# FioSaber.net
KiCad netlist of a schematic drawn in EAGLE
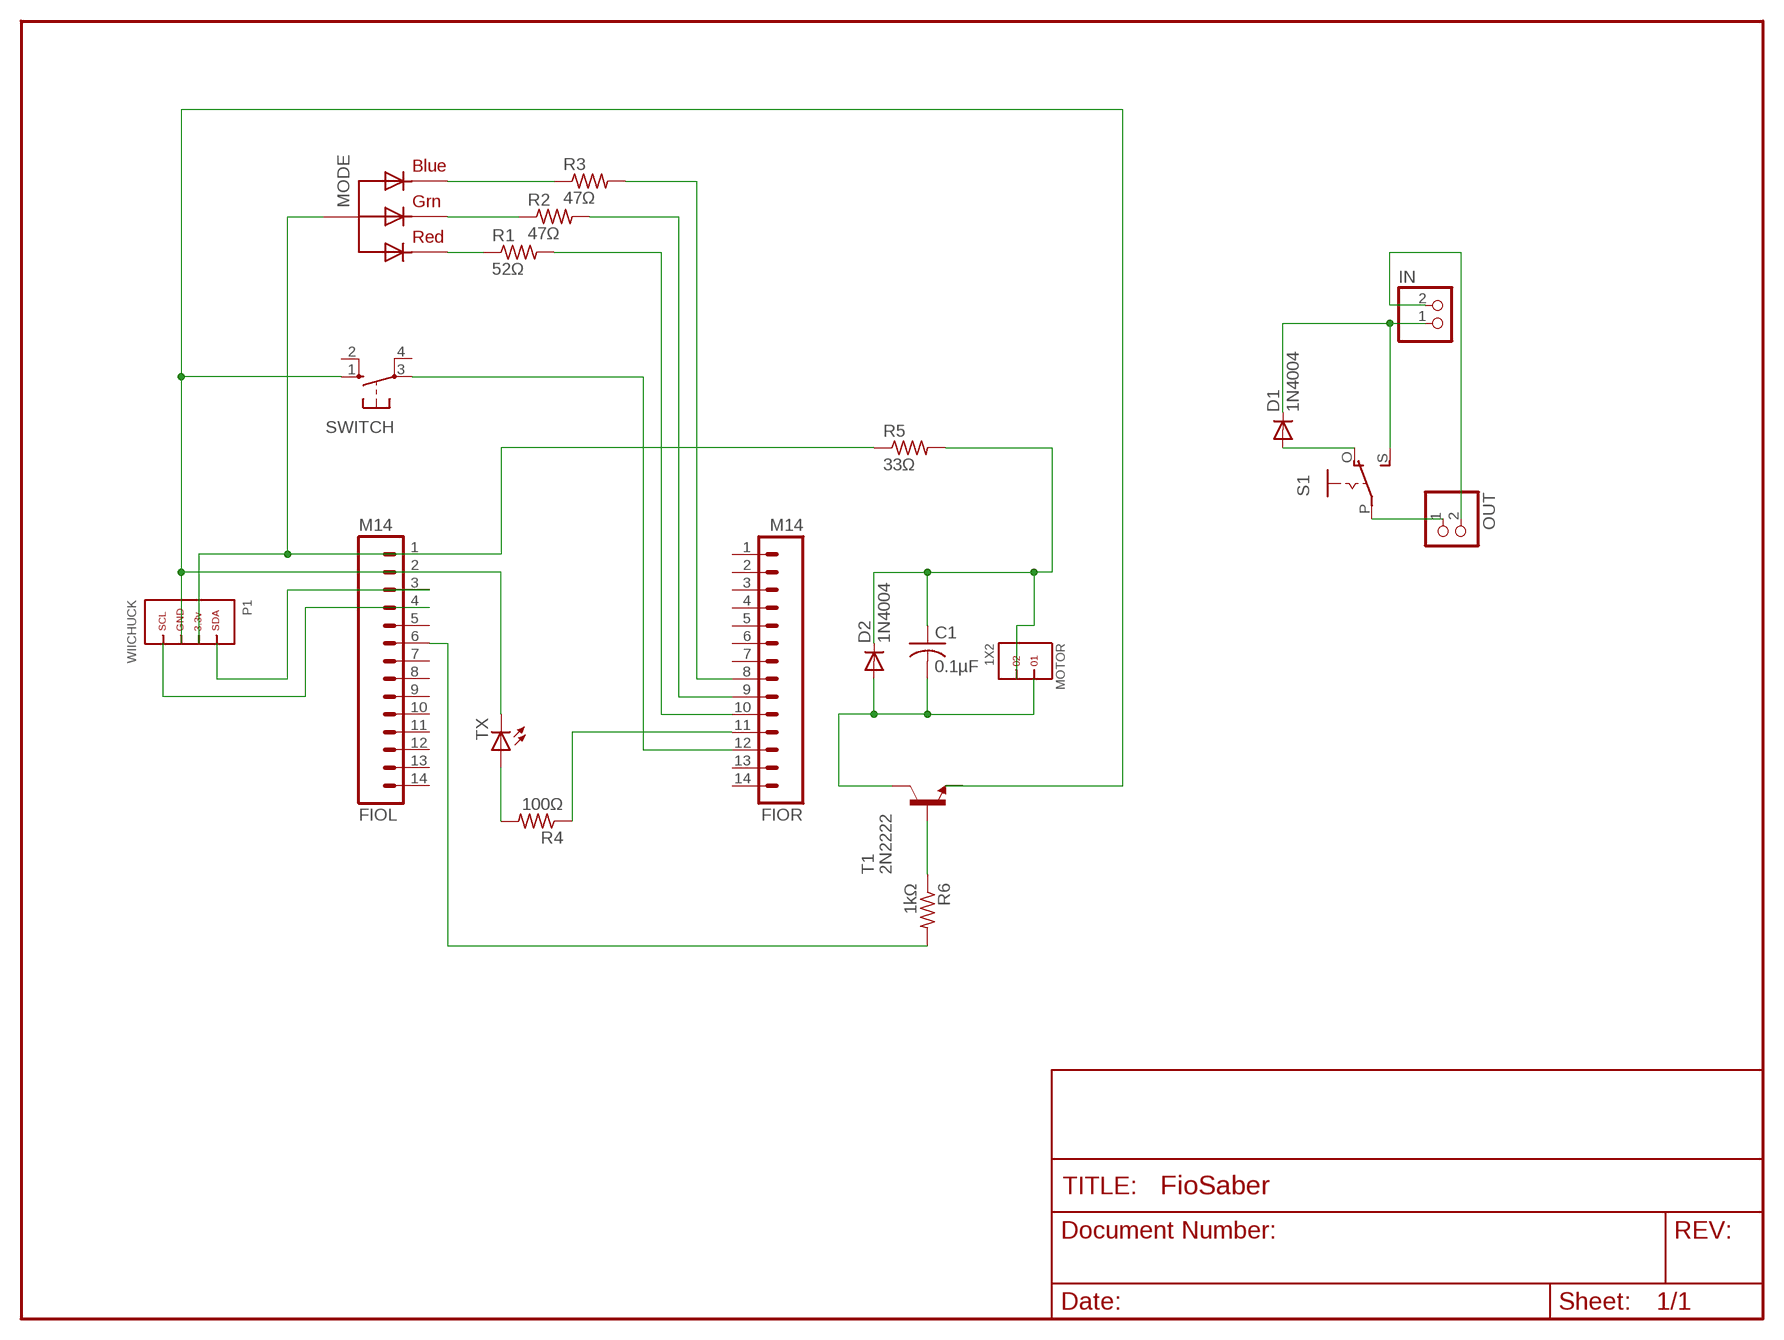
[diagram p0: schematic, sheet 1]

(export (version "E")
  (design (tool "Eeschema 10.0.6"))
  (components
    (comp (ref "C1")
      (value "0.1µF")
      (footprint "eagle-import:C025-025X050")
      (libsource (lib "eagle-import") (part "C-US025-025X050"))
    )
    (comp (ref "D1")
      (value "1N4004")
      (footprint "eagle-import:DO41-10")
      (libsource (lib "eagle-import") (part "1N4004"))
    )
    (comp (ref "D2")
      (value "1N4004")
      (footprint "eagle-import:DO41-10")
      (libsource (lib "eagle-import") (part "1N4004"))
    )
    (comp (ref "FIOL")
      (value "M14")
      (footprint "eagle-import:1X14")
      (libsource (lib "eagle-import") (part "M14"))
    )
    (comp (ref "FIOR")
      (value "M14")
      (footprint "eagle-import:1X14")
      (libsource (lib "eagle-import") (part "M14"))
    )
    (comp (ref "IN")
      (value "JST_2PIN-THM-RA")
      (footprint "eagle-import:JST-PH-2-THM-RA")
      (libsource (lib "eagle-import") (part "JST_2PIN-THM-RA"))
    )
    (comp (ref "MODE")
      (value "RGBLED_CA-PIRANHA")
      (footprint "eagle-import:PIRANHA5MM")
      (libsource (lib "eagle-import") (part "RGBLED_CA-PIRANHA"))
    )
    (comp (ref "MOTOR")
      (value "1X2")
      (footprint "eagle-import:1X2")
      (libsource (lib "eagle-import") (part "1X2"))
    )
    (comp (ref "OUT")
      (value "JST_2PIN-THM-RA")
      (footprint "eagle-import:JST-PH-2-THM-RA")
      (libsource (lib "eagle-import") (part "JST_2PIN-THM-RA"))
    )
    (comp (ref "P1")
      (value "WIICHUCK")
      (footprint "eagle-import:MEMOREX_RECEIVER")
      (libsource (lib "eagle-import") (part "WIICHUCK"))
    )
    (comp (ref "R1")
      (value "52Ω")
      (footprint "eagle-import:0207_7")
      (libsource (lib "eagle-import") (part "R-US_0207/7"))
    )
    (comp (ref "R2")
      (value "47Ω")
      (footprint "eagle-import:0207_7")
      (libsource (lib "eagle-import") (part "R-US_0207/7"))
    )
    (comp (ref "R3")
      (value "47Ω")
      (footprint "eagle-import:0207_7")
      (libsource (lib "eagle-import") (part "R-US_0207/7"))
    )
    (comp (ref "R4")
      (value "100Ω")
      (footprint "eagle-import:0207_7")
      (libsource (lib "eagle-import") (part "R-US_0207/7"))
    )
    (comp (ref "R5")
      (value "33Ω")
      (footprint "eagle-import:0207_7")
      (libsource (lib "eagle-import") (part "R-US_0207/7"))
    )
    (comp (ref "R6")
      (value "1kΩ")
      (footprint "eagle-import:0207_7")
      (libsource (lib "eagle-import") (part "R-US_0207/7"))
    )
    (comp (ref "S1")
      (value "EG1218S")
      (footprint "eagle-import:EG1218")
      (libsource (lib "eagle-import") (part "EG1218S"))
    )
    (comp (ref "SWITCH")
      (value "10-XX")
      (footprint "eagle-import:B3F-10XX")
      (fields (field (name "MPN") "B3F-1000"))
      (libsource (lib "eagle-import") (part "10-XX"))
    )
    (comp (ref "T1")
      (value "2N2222")
      (footprint "eagle-import:TO92-EBC-OVAL")
      (libsource (lib "eagle-import") (part "2N2222"))
    )
    (comp (ref "TX")
      (value "LED3MM")
      (footprint "eagle-import:LED3MM")
      (libsource (lib "eagle-import") (part "LED3MM"))
    )
  )
  (nets
    (net (code "1") (name "Net-(C1-Pad1)") (class "Default")
      (node (ref "C1") (pin "1") (pinfunction "1_1") (pintype "passive"))
      (node (ref "D2") (pin "C") (pinfunction "C_C") (pintype "passive"))
      (node (ref "MOTOR") (pin "2") (pinfunction "2_2") (pintype "bidirectional"))
      (node (ref "R5") (pin "2") (pinfunction "2_2") (pintype "passive"))
    )
    (net (code "2") (name "Net-(C1-Pad2)") (class "Default")
      (node (ref "C1") (pin "2") (pinfunction "2_2") (pintype "passive"))
      (node (ref "D2") (pin "A") (pinfunction "A_A") (pintype "passive"))
      (node (ref "MOTOR") (pin "1") (pinfunction "1_1") (pintype "bidirectional"))
      (node (ref "T1") (pin "C") (pinfunction "C_C") (pintype "passive"))
    )
    (net (code "3") (name "Net-(D1-PadA)") (class "Default")
      (node (ref "D1") (pin "A") (pinfunction "A_A") (pintype "passive"))
      (node (ref "S1") (pin "O") (pinfunction "O_O") (pintype "passive"))
    )
    (net (code "4") (name "Net-(FIOL-Pad3)") (class "Default")
      (node (ref "FIOL") (pin "3") (pinfunction "3_3") (pintype "passive"))
      (node (ref "P1") (pin "PWR") (pinfunction "PWR_PWR") (pintype "bidirectional"))
    )
    (net (code "5") (name "Net-(FIOL-Pad4)") (class "Default")
      (node (ref "FIOL") (pin "4") (pinfunction "4_4") (pintype "passive"))
      (node (ref "P1") (pin "GND") (pinfunction "GND_GND") (pintype "bidirectional"))
    )
    (net (code "6") (name "Net-(FIOL-Pad6)") (class "Default")
      (node (ref "FIOL") (pin "6") (pinfunction "6_6") (pintype "passive"))
      (node (ref "R6") (pin "2") (pinfunction "2_2") (pintype "passive"))
    )
    (net (code "7") (name "Net-(FIOR-Pad8)") (class "Default")
      (node (ref "FIOR") (pin "8") (pinfunction "8_8") (pintype "passive"))
      (node (ref "R3") (pin "2") (pinfunction "2_2") (pintype "passive"))
    )
    (net (code "8") (name "Net-(FIOR-Pad9)") (class "Default")
      (node (ref "FIOR") (pin "9") (pinfunction "9_9") (pintype "passive"))
      (node (ref "R2") (pin "2") (pinfunction "2_2") (pintype "passive"))
    )
    (net (code "9") (name "Net-(FIOR-Pad10)") (class "Default")
      (node (ref "FIOR") (pin "10") (pinfunction "10_10") (pintype "passive"))
      (node (ref "R1") (pin "2") (pinfunction "2_2") (pintype "passive"))
    )
    (net (code "10") (name "Net-(FIOR-Pad11)") (class "Default")
      (node (ref "FIOR") (pin "11") (pinfunction "11_11") (pintype "passive"))
      (node (ref "R4") (pin "1") (pinfunction "1_1") (pintype "passive"))
    )
    (net (code "11") (name "Net-(IN-1)") (class "Default")
      (node (ref "IN") (pin "2") (pinfunction "1_2") (pintype "passive"))
      (node (ref "OUT") (pin "2") (pinfunction "1_2") (pintype "passive"))
    )
    (net (code "12") (name "Net-(IN-2)") (class "Default")
      (node (ref "D1") (pin "C") (pinfunction "C_C") (pintype "passive"))
      (node (ref "IN") (pin "1") (pinfunction "2_1") (pintype "passive"))
      (node (ref "S1") (pin "S") (pinfunction "S_S") (pintype "passive"))
    )
    (net (code "13") (name "Net-(MODE-BLUE)") (class "Default")
      (node (ref "MODE") (pin "1") (pinfunction "BLUE_1") (pintype "bidirectional"))
      (node (ref "R3") (pin "1") (pinfunction "1_1") (pintype "passive"))
    )
    (net (code "14") (name "Net-(MODE-GREEN)") (class "Default")
      (node (ref "MODE") (pin "3") (pinfunction "GREEN_3") (pintype "bidirectional"))
      (node (ref "R2") (pin "1") (pinfunction "1_1") (pintype "passive"))
    )
    (net (code "15") (name "Net-(MODE-RED)") (class "Default")
      (node (ref "MODE") (pin "2") (pinfunction "RED_2") (pintype "bidirectional"))
      (node (ref "R1") (pin "1") (pinfunction "1_1") (pintype "passive"))
    )
    (net (code "16") (name "Net-(MODE-VCC)") (class "Default")
      (node (ref "FIOL") (pin "1") (pinfunction "1_1") (pintype "passive"))
      (node (ref "MODE") (pin "4") (pinfunction "VCC_4") (pintype "bidirectional"))
      (node (ref "P1") (pin "SDA") (pinfunction "SDA_SDA") (pintype "bidirectional"))
      (node (ref "R5") (pin "1") (pinfunction "1_1") (pintype "passive"))
    )
    (net (code "17") (name "Net-(OUT-2)") (class "Default")
      (node (ref "OUT") (pin "1") (pinfunction "2_1") (pintype "passive"))
      (node (ref "S1") (pin "P") (pinfunction "P_P") (pintype "passive"))
    )
    (net (code "18") (name "Net-(R4-Pad2)") (class "Default")
      (node (ref "R4") (pin "2") (pinfunction "2_2") (pintype "passive"))
      (node (ref "TX") (pin "A") (pinfunction "A_A") (pintype "passive"))
    )
    (net (code "19") (name "Net-(R6-Pad1)") (class "Default")
      (node (ref "R6") (pin "1") (pinfunction "1_1") (pintype "passive"))
      (node (ref "T1") (pin "B") (pinfunction "B_B") (pintype "passive"))
    )
    (net (code "20") (name "Net-(SWITCH-P)") (class "Default")
      (node (ref "FIOR") (pin "12") (pinfunction "12_12") (pintype "passive"))
      (node (ref "SWITCH") (pin "3") (pinfunction "P_3") (pintype "passive"))
    )
    (net (code "21") (name "Net-(SWITCH-S)") (class "Default")
      (node (ref "FIOL") (pin "2") (pinfunction "2_2") (pintype "passive"))
      (node (ref "P1") (pin "SCL") (pinfunction "SCL_SCL") (pintype "bidirectional"))
      (node (ref "SWITCH") (pin "1") (pinfunction "S_1") (pintype "passive"))
      (node (ref "TX") (pin "K") (pinfunction "C_K") (pintype "passive"))
    )
    (net (code "22") (name "unconnected-(FIOL-Pad5)") (class "Default")
      (node (ref "FIOL") (pin "5") (pinfunction "5_5") (pintype "passive"))
    )
    (net (code "23") (name "unconnected-(FIOL-Pad7)") (class "Default")
      (node (ref "FIOL") (pin "7") (pinfunction "7_7") (pintype "passive"))
    )
    (net (code "24") (name "unconnected-(FIOL-Pad8)") (class "Default")
      (node (ref "FIOL") (pin "8") (pinfunction "8_8") (pintype "passive"))
    )
    (net (code "25") (name "unconnected-(FIOL-Pad9)") (class "Default")
      (node (ref "FIOL") (pin "9") (pinfunction "9_9") (pintype "passive"))
    )
    (net (code "26") (name "unconnected-(FIOL-Pad10)") (class "Default")
      (node (ref "FIOL") (pin "10") (pinfunction "10_10") (pintype "passive"))
    )
    (net (code "27") (name "unconnected-(FIOL-Pad11)") (class "Default")
      (node (ref "FIOL") (pin "11") (pinfunction "11_11") (pintype "passive"))
    )
    (net (code "28") (name "unconnected-(FIOL-Pad12)") (class "Default")
      (node (ref "FIOL") (pin "12") (pinfunction "12_12") (pintype "passive"))
    )
    (net (code "29") (name "unconnected-(FIOL-Pad13)") (class "Default")
      (node (ref "FIOL") (pin "13") (pinfunction "13_13") (pintype "passive"))
    )
    (net (code "30") (name "unconnected-(FIOL-Pad14)") (class "Default")
      (node (ref "FIOL") (pin "14") (pinfunction "14_14") (pintype "passive"))
    )
    (net (code "31") (name "unconnected-(FIOR-Pad1)") (class "Default")
      (node (ref "FIOR") (pin "1") (pinfunction "1_1") (pintype "passive"))
    )
    (net (code "32") (name "unconnected-(FIOR-Pad2)") (class "Default")
      (node (ref "FIOR") (pin "2") (pinfunction "2_2") (pintype "passive"))
    )
    (net (code "33") (name "unconnected-(FIOR-Pad3)") (class "Default")
      (node (ref "FIOR") (pin "3") (pinfunction "3_3") (pintype "passive"))
    )
    (net (code "34") (name "unconnected-(FIOR-Pad4)") (class "Default")
      (node (ref "FIOR") (pin "4") (pinfunction "4_4") (pintype "passive"))
    )
    (net (code "35") (name "unconnected-(FIOR-Pad5)") (class "Default")
      (node (ref "FIOR") (pin "5") (pinfunction "5_5") (pintype "passive"))
    )
    (net (code "36") (name "unconnected-(FIOR-Pad6)") (class "Default")
      (node (ref "FIOR") (pin "6") (pinfunction "6_6") (pintype "passive"))
    )
    (net (code "37") (name "unconnected-(FIOR-Pad7)") (class "Default")
      (node (ref "FIOR") (pin "7") (pinfunction "7_7") (pintype "passive"))
    )
    (net (code "38") (name "unconnected-(FIOR-Pad13)") (class "Default")
      (node (ref "FIOR") (pin "13") (pinfunction "13_13") (pintype "passive"))
    )
    (net (code "39") (name "unconnected-(FIOR-Pad14)") (class "Default")
      (node (ref "FIOR") (pin "14") (pinfunction "14_14") (pintype "passive"))
    )
    (net (code "40") (name "unconnected-(SWITCH-P1-Pad4)") (class "Default")
      (node (ref "SWITCH") (pin "4") (pinfunction "P1_4") (pintype "passive"))
    )
    (net (code "41") (name "unconnected-(SWITCH-S1-Pad2)") (class "Default")
      (node (ref "SWITCH") (pin "2") (pinfunction "S1_2") (pintype "passive"))
    )
    (net (code "42") (name "unconnected-(T1-PadE)") (class "Default")
      (node (ref "T1") (pin "E") (pinfunction "E_E") (pintype "passive"))
    )
  )
)
